# leds.net
KiCad netlist of a schematic drawn in EAGLE
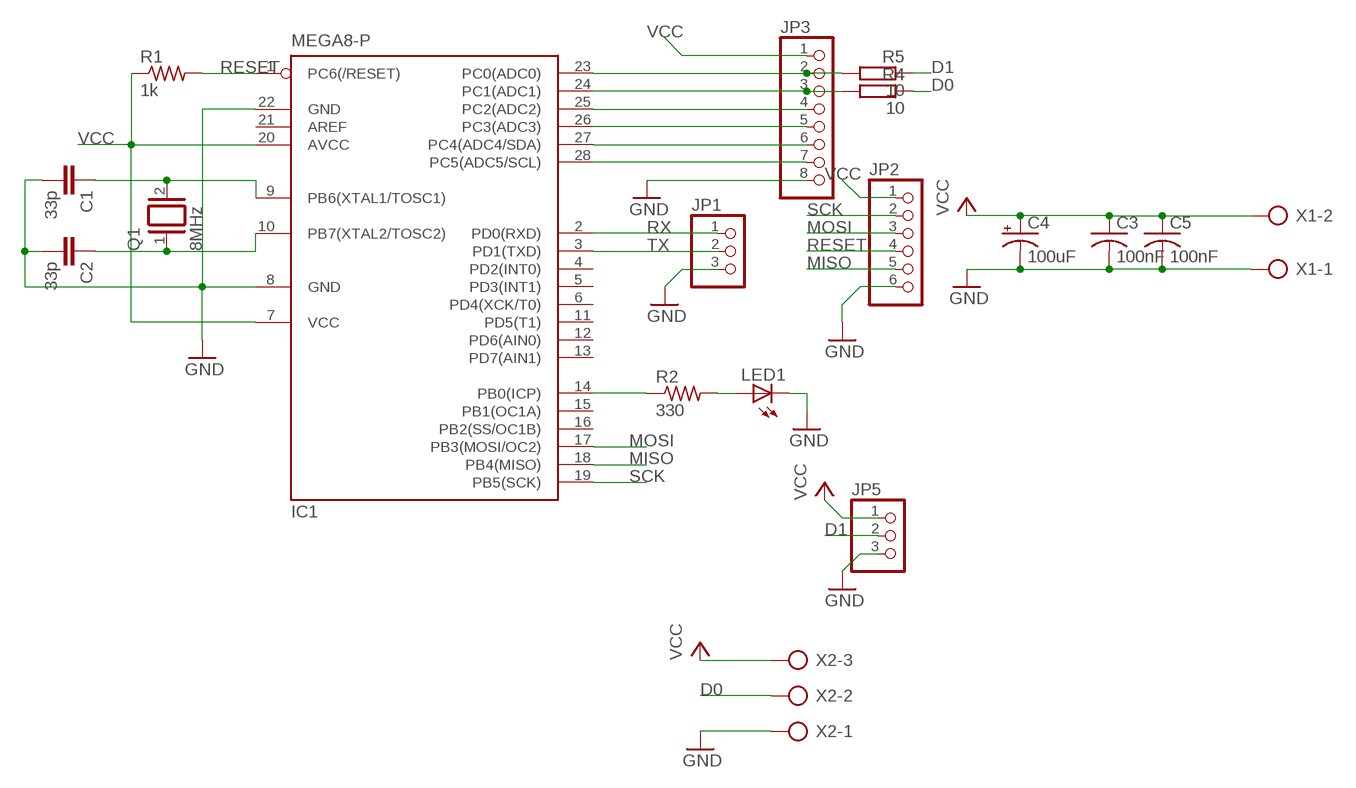
[diagram p0: schematic, sheet 1]

(export (version "E")
  (design (tool "Eeschema 10.0.6"))
  (components
    (comp (ref "C1")
      (value "33p")
      (footprint "eagle-import:C025-025X050")
      (libsource (lib "eagle-import") (part "C-EU025-025X050"))
    )
    (comp (ref "C2")
      (value "33p")
      (footprint "eagle-import:C025-025X050")
      (libsource (lib "eagle-import") (part "C-EU025-025X050"))
    )
    (comp (ref "C3")
      (value "100nF")
      (footprint "eagle-import:C0805")
      (libsource (lib "eagle-import") (part "C-USC0805"))
    )
    (comp (ref "C4")
      (value "100uF")
      (footprint "eagle-import:E5-8,5")
      (libsource (lib "eagle-import") (part "CPOL-USE5-8.5"))
    )
    (comp (ref "C5")
      (value "100nF")
      (footprint "eagle-import:C0805")
      (libsource (lib "eagle-import") (part "C-USC0805"))
    )
    (comp (ref "IC1")
      (value "MEGA8-P")
      (footprint "eagle-import:DIL28-3")
      (libsource (lib "eagle-import") (part "MEGA8-P"))
    )
    (comp (ref "JP1")
      (value "PINHD-1X3")
      (footprint "eagle-import:1X03")
      (libsource (lib "eagle-import") (part "PINHD-1X3"))
    )
    (comp (ref "JP2")
      (value "PINHD-1X6")
      (footprint "eagle-import:1X06")
      (libsource (lib "eagle-import") (part "PINHD-1X6"))
    )
    (comp (ref "JP3")
      (value "PINHD-1X8")
      (footprint "eagle-import:1X08")
      (libsource (lib "eagle-import") (part "PINHD-1X8"))
    )
    (comp (ref "JP5")
      (value "PINHD-1X3")
      (footprint "eagle-import:1X03")
      (libsource (lib "eagle-import") (part "PINHD-1X3"))
    )
    (comp (ref "LED1")
      (value "LED3MM")
      (footprint "eagle-import:LED3MM")
      (libsource (lib "eagle-import") (part "LED3MM"))
    )
    (comp (ref "Q1")
      (value "8MHz")
      (footprint "eagle-import:QS")
      (libsource (lib "eagle-import") (part "XTAL/S"))
    )
    (comp (ref "R1")
      (value "1k")
      (footprint "eagle-import:M0805")
      (libsource (lib "eagle-import") (part "R-US_M0805"))
    )
    (comp (ref "R2")
      (value "330")
      (footprint "eagle-import:M0805")
      (libsource (lib "eagle-import") (part "R-US_M0805"))
    )
    (comp (ref "R4")
      (value "10")
      (footprint "eagle-import:0204_7")
      (libsource (lib "eagle-import") (part "R-EU_0204/7"))
    )
    (comp (ref "R5")
      (value "10")
      (footprint "eagle-import:0204_7")
      (libsource (lib "eagle-import") (part "R-EU_0204/7"))
    )
    (comp (ref "X1")
      (value "AK500/2")
      (footprint "eagle-import:AK500_2")
      (libsource (lib "eagle-import") (part "AK500/2"))
    )
    (comp (ref "X2")
      (value "AK500/3")
      (footprint "eagle-import:AK500_3")
      (libsource (lib "eagle-import") (part "AK500/3"))
    )
  )
  (nets
    (net (code "1") (name "/D0") (class "Default")
      (node (ref "R4") (pin "1") (pinfunction "1_1") (pintype "passive"))
      (node (ref "X2") (pin "2") (pinfunction "KL_2") (pintype "passive"))
    )
    (net (code "2") (name "/D1") (class "Default")
      (node (ref "JP5") (pin "2") (pinfunction "2_2") (pintype "passive"))
      (node (ref "R5") (pin "1") (pinfunction "1_1") (pintype "passive"))
    )
    (net (code "3") (name "/MISO") (class "Default")
      (node (ref "IC1") (pin "18") (pinfunction "PB4(MISO)_18") (pintype "bidirectional"))
      (node (ref "JP2") (pin "5") (pinfunction "5_5") (pintype "passive"))
    )
    (net (code "4") (name "/MOSI") (class "Default")
      (node (ref "IC1") (pin "17") (pinfunction "PB3(MOSI/OC2)_17") (pintype "bidirectional"))
      (node (ref "JP2") (pin "3") (pinfunction "3_3") (pintype "passive"))
    )
    (net (code "5") (name "/RESET") (class "Default")
      (node (ref "IC1") (pin "1") (pinfunction "PC6(/RESET)_1") (pintype "bidirectional"))
      (node (ref "JP2") (pin "4") (pinfunction "4_4") (pintype "passive"))
      (node (ref "R1") (pin "2") (pinfunction "2_2") (pintype "passive"))
    )
    (net (code "6") (name "/RX") (class "Default")
      (node (ref "IC1") (pin "2") (pinfunction "PD0(RXD)_2") (pintype "bidirectional"))
      (node (ref "JP1") (pin "1") (pinfunction "1_1") (pintype "passive"))
    )
    (net (code "7") (name "/SCK") (class "Default")
      (node (ref "IC1") (pin "19") (pinfunction "PB5(SCK)_19") (pintype "bidirectional"))
      (node (ref "JP2") (pin "2") (pinfunction "2_2") (pintype "passive"))
    )
    (net (code "8") (name "/TX") (class "Default")
      (node (ref "IC1") (pin "3") (pinfunction "PD1(TXD)_3") (pintype "bidirectional"))
      (node (ref "JP1") (pin "2") (pinfunction "2_2") (pintype "passive"))
    )
    (net (code "9") (name "GND") (class "Default")
      (node (ref "C1") (pin "2") (pinfunction "2_2") (pintype "passive"))
      (node (ref "C2") (pin "2") (pinfunction "2_2") (pintype "passive"))
      (node (ref "C3") (pin "2") (pinfunction "2_2") (pintype "passive"))
      (node (ref "C4") (pin "-") (pinfunction "-_-") (pintype "passive"))
      (node (ref "C5") (pin "2") (pinfunction "2_2") (pintype "passive"))
      (node (ref "IC1") (pin "22") (pinfunction "GND_22") (pintype "power_in"))
      (node (ref "IC1") (pin "8") (pinfunction "GND_8") (pintype "power_in"))
      (node (ref "JP1") (pin "3") (pinfunction "3_3") (pintype "passive"))
      (node (ref "JP2") (pin "6") (pinfunction "6_6") (pintype "passive"))
      (node (ref "JP3") (pin "8") (pinfunction "8_8") (pintype "passive"))
      (node (ref "JP5") (pin "3") (pinfunction "3_3") (pintype "passive"))
      (node (ref "LED1") (pin "K") (pinfunction "C_K") (pintype "passive"))
      (node (ref "X1") (pin "1") (pinfunction "KL_1") (pintype "passive"))
      (node (ref "X2") (pin "1") (pinfunction "KL_1") (pintype "passive"))
    )
    (net (code "10") (name "Net-(IC1-PB0(ICP))") (class "Default")
      (node (ref "IC1") (pin "14") (pinfunction "PB0(ICP)_14") (pintype "bidirectional"))
      (node (ref "R2") (pin "1") (pinfunction "1_1") (pintype "passive"))
    )
    (net (code "11") (name "Net-(IC1-PB6(XTAL1{slash}TOSC1))") (class "Default")
      (node (ref "C1") (pin "1") (pinfunction "1_1") (pintype "passive"))
      (node (ref "IC1") (pin "9") (pinfunction "PB6(XTAL1/TOSC1)_9") (pintype "bidirectional"))
      (node (ref "Q1") (pin "2") (pinfunction "2_2") (pintype "passive"))
    )
    (net (code "12") (name "Net-(IC1-PB7(XTAL2{slash}TOSC2))") (class "Default")
      (node (ref "C2") (pin "1") (pinfunction "1_1") (pintype "passive"))
      (node (ref "IC1") (pin "10") (pinfunction "PB7(XTAL2/TOSC2)_10") (pintype "bidirectional"))
      (node (ref "Q1") (pin "1") (pinfunction "1_1") (pintype "passive"))
    )
    (net (code "13") (name "Net-(IC1-PC0(ADC0))") (class "Default")
      (node (ref "IC1") (pin "23") (pinfunction "PC0(ADC0)_23") (pintype "bidirectional"))
      (node (ref "JP3") (pin "2") (pinfunction "2_2") (pintype "passive"))
      (node (ref "R5") (pin "2") (pinfunction "2_2") (pintype "passive"))
    )
    (net (code "14") (name "Net-(IC1-PC1(ADC1))") (class "Default")
      (node (ref "IC1") (pin "24") (pinfunction "PC1(ADC1)_24") (pintype "bidirectional"))
      (node (ref "JP3") (pin "3") (pinfunction "3_3") (pintype "passive"))
      (node (ref "R4") (pin "2") (pinfunction "2_2") (pintype "passive"))
    )
    (net (code "15") (name "Net-(IC1-PC2(ADC2))") (class "Default")
      (node (ref "IC1") (pin "25") (pinfunction "PC2(ADC2)_25") (pintype "bidirectional"))
      (node (ref "JP3") (pin "4") (pinfunction "4_4") (pintype "passive"))
    )
    (net (code "16") (name "Net-(IC1-PC3(ADC3))") (class "Default")
      (node (ref "IC1") (pin "26") (pinfunction "PC3(ADC3)_26") (pintype "bidirectional"))
      (node (ref "JP3") (pin "5") (pinfunction "5_5") (pintype "passive"))
    )
    (net (code "17") (name "Net-(IC1-PC4(ADC4{slash}SDA))") (class "Default")
      (node (ref "IC1") (pin "27") (pinfunction "PC4(ADC4/SDA)_27") (pintype "bidirectional"))
      (node (ref "JP3") (pin "6") (pinfunction "6_6") (pintype "passive"))
    )
    (net (code "18") (name "Net-(IC1-PC5(ADC5{slash}SCL))") (class "Default")
      (node (ref "IC1") (pin "28") (pinfunction "PC5(ADC5/SCL)_28") (pintype "bidirectional"))
      (node (ref "JP3") (pin "7") (pinfunction "7_7") (pintype "passive"))
    )
    (net (code "19") (name "Net-(LED1-PadA)") (class "Default")
      (node (ref "LED1") (pin "A") (pinfunction "A_A") (pintype "passive"))
      (node (ref "R2") (pin "2") (pinfunction "2_2") (pintype "passive"))
    )
    (net (code "20") (name "VCC") (class "Default")
      (node (ref "C3") (pin "1") (pinfunction "1_1") (pintype "passive"))
      (node (ref "C4") (pin "+") (pinfunction "+_+") (pintype "passive"))
      (node (ref "C5") (pin "1") (pinfunction "1_1") (pintype "passive"))
      (node (ref "IC1") (pin "20") (pinfunction "AVCC_20") (pintype "power_in"))
      (node (ref "IC1") (pin "7") (pinfunction "VCC_7") (pintype "power_in"))
      (node (ref "JP2") (pin "1") (pinfunction "1_1") (pintype "passive"))
      (node (ref "JP3") (pin "1") (pinfunction "1_1") (pintype "passive"))
      (node (ref "JP5") (pin "1") (pinfunction "1_1") (pintype "passive"))
      (node (ref "R1") (pin "1") (pinfunction "1_1") (pintype "passive"))
      (node (ref "X1") (pin "2") (pinfunction "KL_2") (pintype "passive"))
      (node (ref "X2") (pin "3") (pinfunction "KL_3") (pintype "passive"))
    )
    (net (code "21") (name "unconnected-(IC1-AREF-Pad21)") (class "Default")
      (node (ref "IC1") (pin "21") (pinfunction "AREF_21") (pintype "passive"))
    )
    (net (code "22") (name "unconnected-(IC1-PB1(OC1A)-Pad15)") (class "Default")
      (node (ref "IC1") (pin "15") (pinfunction "PB1(OC1A)_15") (pintype "bidirectional"))
    )
    (net (code "23") (name "unconnected-(IC1-PB2(SS{slash}OC1B)-Pad16)") (class "Default")
      (node (ref "IC1") (pin "16") (pinfunction "PB2(SS/OC1B)_16") (pintype "bidirectional"))
    )
    (net (code "24") (name "unconnected-(IC1-PD2(INT0)-Pad4)") (class "Default")
      (node (ref "IC1") (pin "4") (pinfunction "PD2(INT0)_4") (pintype "bidirectional"))
    )
    (net (code "25") (name "unconnected-(IC1-PD3(INT1)-Pad5)") (class "Default")
      (node (ref "IC1") (pin "5") (pinfunction "PD3(INT1)_5") (pintype "bidirectional"))
    )
    (net (code "26") (name "unconnected-(IC1-PD4(XCK{slash}T0)-Pad6)") (class "Default")
      (node (ref "IC1") (pin "6") (pinfunction "PD4(XCK/T0)_6") (pintype "bidirectional"))
    )
    (net (code "27") (name "unconnected-(IC1-PD5(T1)-Pad11)") (class "Default")
      (node (ref "IC1") (pin "11") (pinfunction "PD5(T1)_11") (pintype "bidirectional"))
    )
    (net (code "28") (name "unconnected-(IC1-PD6(AIN0)-Pad12)") (class "Default")
      (node (ref "IC1") (pin "12") (pinfunction "PD6(AIN0)_12") (pintype "bidirectional"))
    )
    (net (code "29") (name "unconnected-(IC1-PD7(AIN1)-Pad13)") (class "Default")
      (node (ref "IC1") (pin "13") (pinfunction "PD7(AIN1)_13") (pintype "bidirectional"))
    )
  )
)
